# 8EncV1_3_3.net
KiCad netlist of a schematic drawn in EAGLE
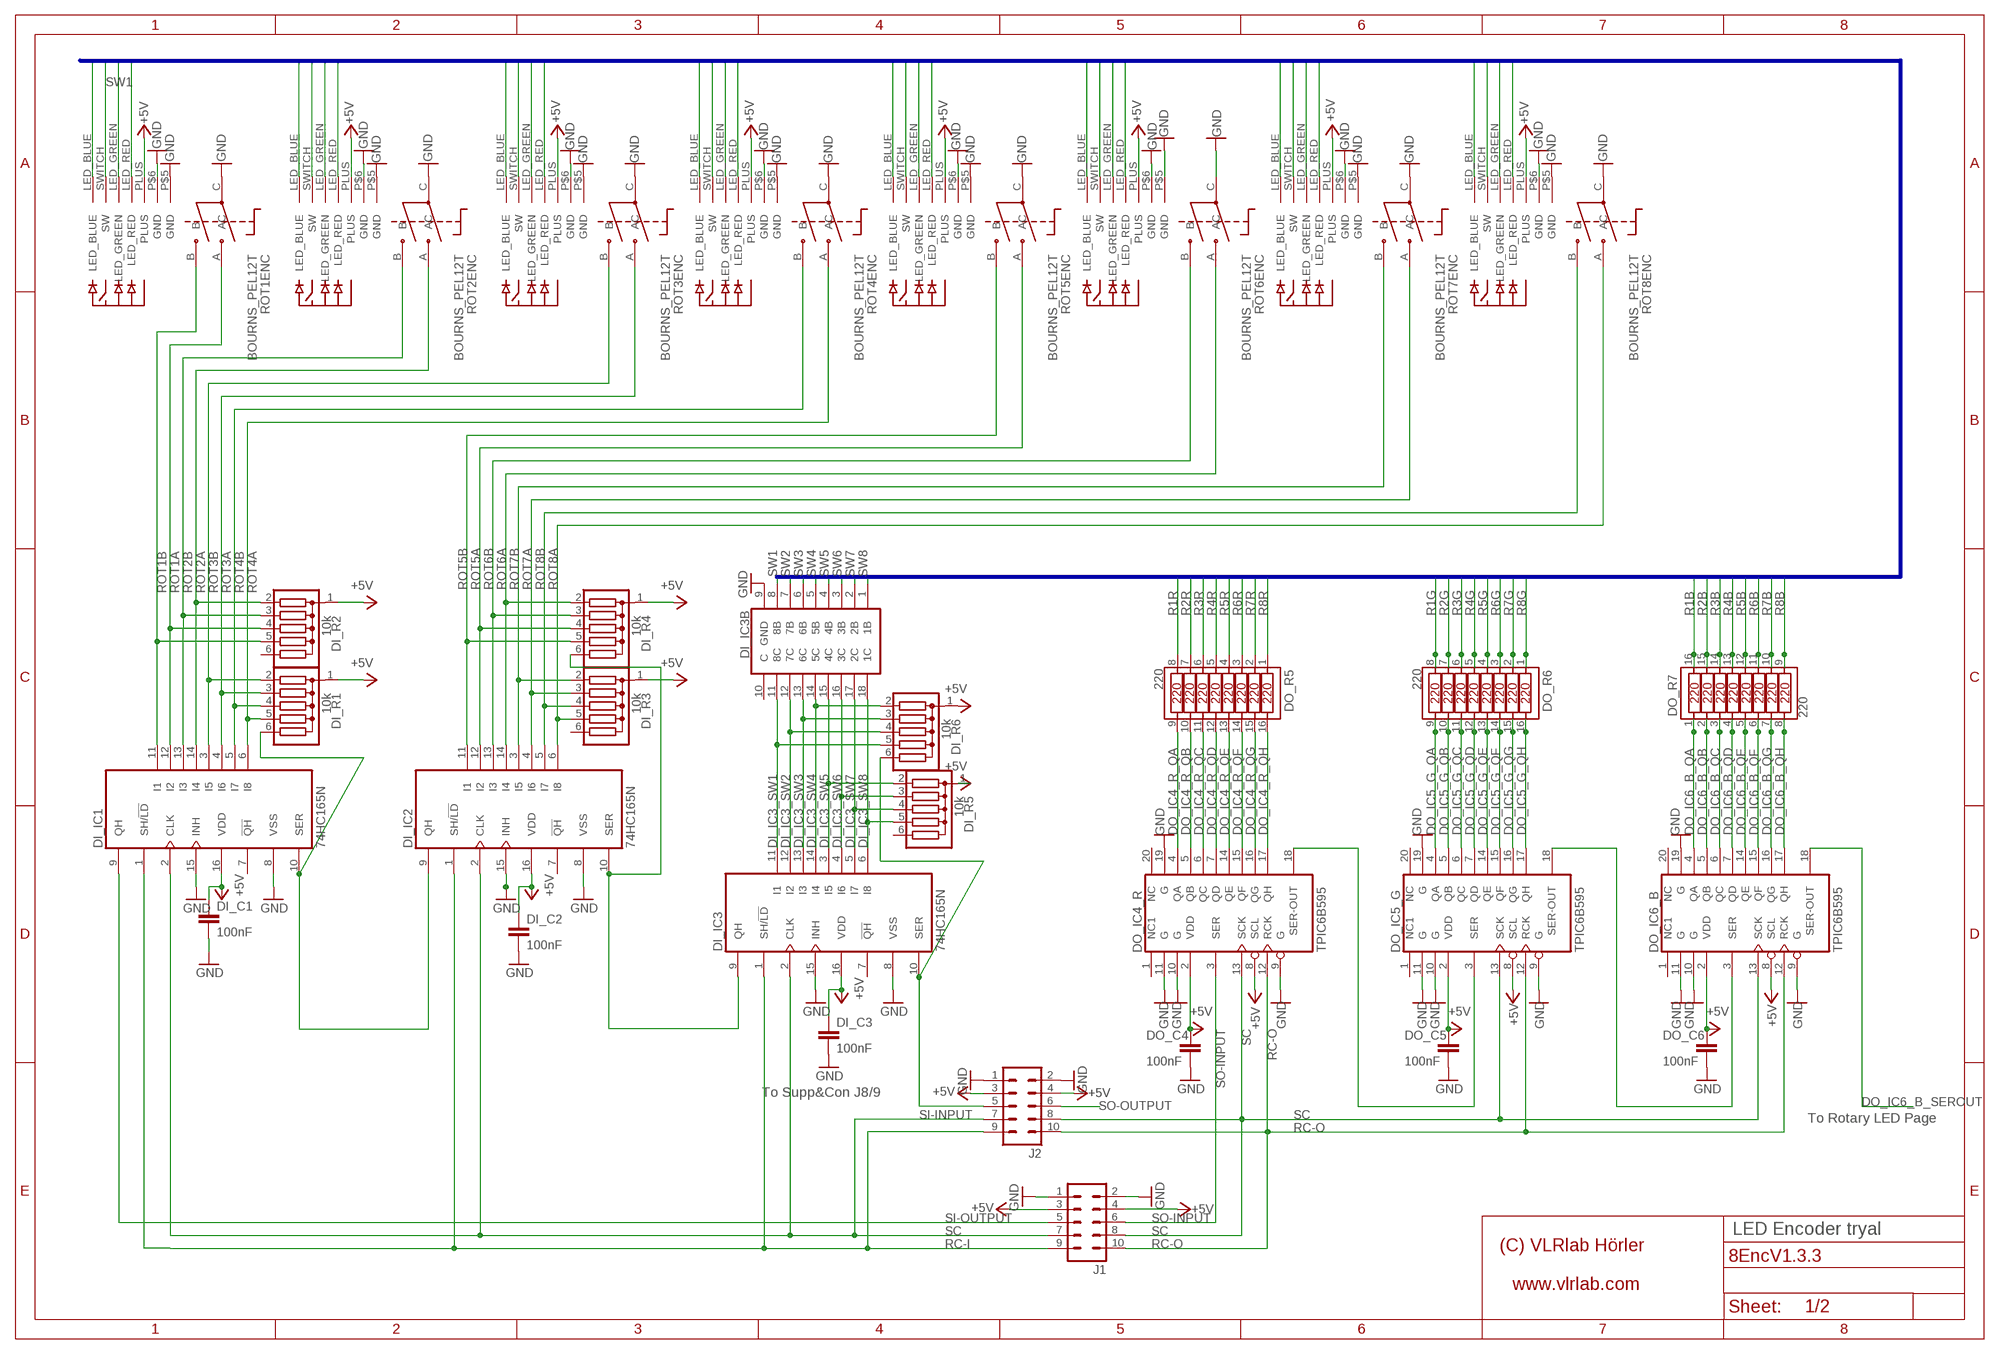
[diagram p0: schematic, sheet 1]
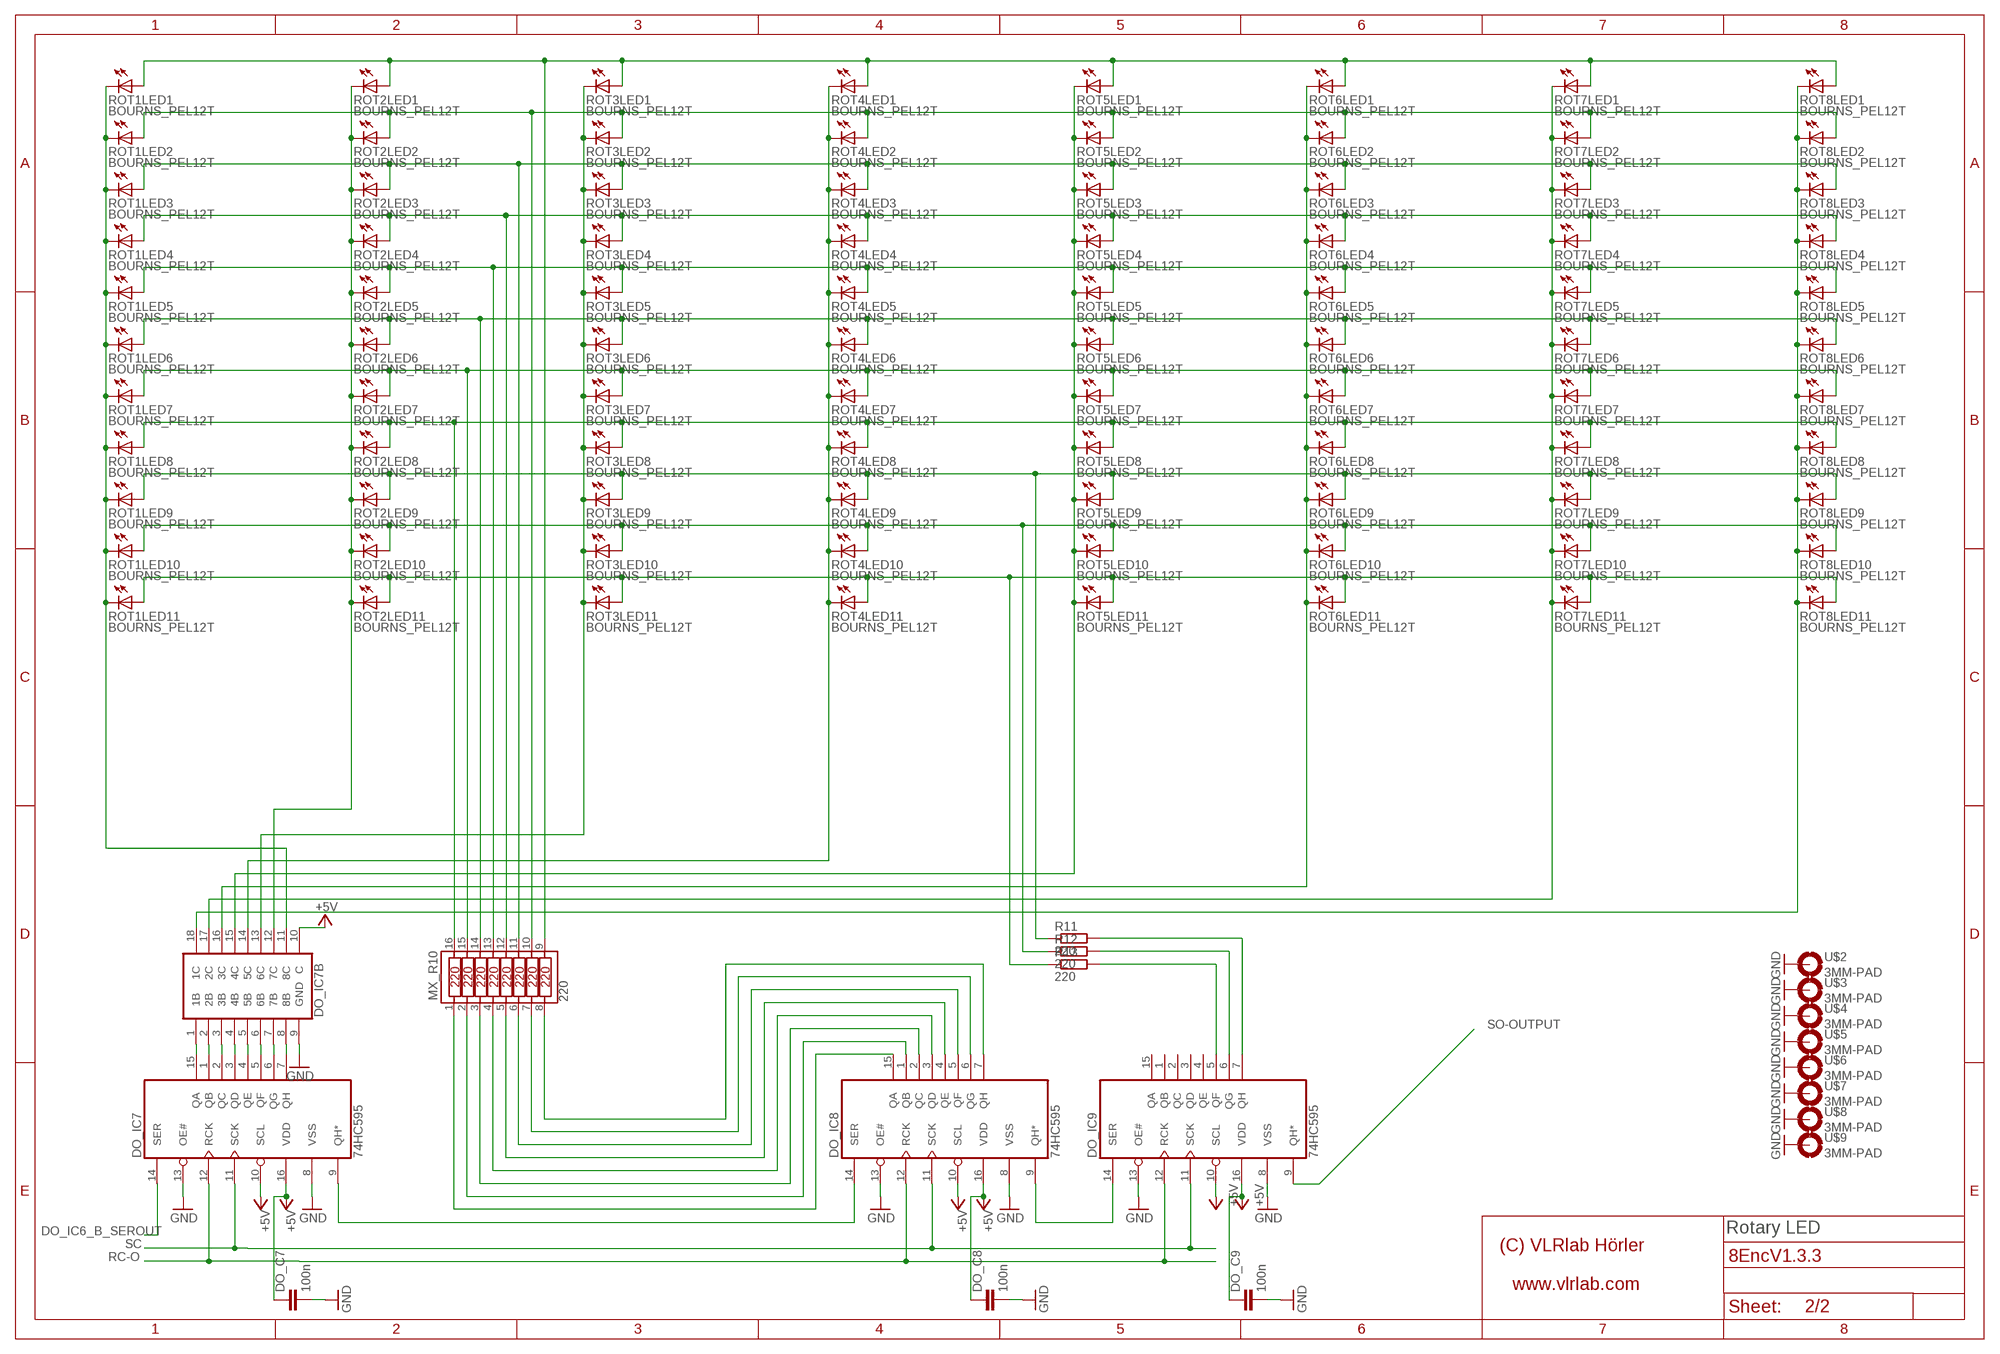
[diagram p1: schematic, sheet 2]

(export (version "E")
  (design (tool "Eeschema 10.0.6"))
  (components
    (comp (ref "DO_C7")
      (value "100n")
      (footprint "eagle-import:C025-024X044")
      (libsource (lib "eagle-import") (part "C-EU025-024X044"))
    )
    (comp (ref "DO_C8")
      (value "100n")
      (footprint "eagle-import:C025-024X044")
      (libsource (lib "eagle-import") (part "C-EU025-024X044"))
    )
    (comp (ref "DO_C9")
      (value "100n")
      (footprint "eagle-import:C025-024X044")
      (libsource (lib "eagle-import") (part "C-EU025-024X044"))
    )
    (comp (ref "DO_IC7")
      (value "74HC595")
      (footprint "eagle-import:SO16D")
      (libsource (lib "eagle-import") (part "595-541-165-uln2803_74HC595SO16D"))
    )
    (comp (ref "DO_IC7B")
      (value "ULN2803SO18W")
      (footprint "eagle-import:SO18W")
      (libsource (lib "eagle-import") (part "ULN2803SO18W"))
    )
    (comp (ref "DO_IC8")
      (value "74HC595")
      (footprint "eagle-import:SO16D")
      (libsource (lib "eagle-import") (part "595-541-165-uln2803_74HC595SO16D"))
    )
    (comp (ref "DO_IC9")
      (value "74HC595")
      (footprint "eagle-import:SO16D")
      (libsource (lib "eagle-import") (part "595-541-165-uln2803_74HC595SO16D"))
    )
    (comp (ref "MX_R10")
      (value "220")
      (footprint "eagle-import:SOIC16W")
      (libsource (lib "eagle-import") (part "4816P-1SOIC16W"))
    )
    (comp (ref "R11")
      (value "220")
      (footprint "eagle-import:0204_7")
      (libsource (lib "eagle-import") (part "R-EU_0204/7"))
    )
    (comp (ref "R12")
      (value "220")
      (footprint "eagle-import:0204_7")
      (libsource (lib "eagle-import") (part "R-EU_0204/7"))
    )
    (comp (ref "R13")
      (value "220")
      (footprint "eagle-import:0204_7")
      (libsource (lib "eagle-import") (part "R-EU_0204/7"))
    )
    (comp (ref "ROT1")
      (value "BOURNS_PEL12T")
      (footprint "eagle-import:PEL12T_11-LED-RING")
      (libsource (lib "eagle-import") (part "BOURNS_PEL12T_11-LED-RING"))
    )
    (comp (ref "ROT2")
      (value "BOURNS_PEL12T")
      (footprint "eagle-import:PEL12T_11-LED-RING")
      (libsource (lib "eagle-import") (part "BOURNS_PEL12T_11-LED-RING"))
    )
    (comp (ref "ROT3")
      (value "BOURNS_PEL12T")
      (footprint "eagle-import:PEL12T_11-LED-RING")
      (libsource (lib "eagle-import") (part "BOURNS_PEL12T_11-LED-RING"))
    )
    (comp (ref "ROT4")
      (value "BOURNS_PEL12T")
      (footprint "eagle-import:PEL12T_11-LED-RING")
      (libsource (lib "eagle-import") (part "BOURNS_PEL12T_11-LED-RING"))
    )
    (comp (ref "ROT5")
      (value "BOURNS_PEL12T")
      (footprint "eagle-import:PEL12T_11-LED-RING")
      (libsource (lib "eagle-import") (part "BOURNS_PEL12T_11-LED-RING"))
    )
    (comp (ref "ROT6")
      (value "BOURNS_PEL12T")
      (footprint "eagle-import:PEL12T_11-LED-RING")
      (libsource (lib "eagle-import") (part "BOURNS_PEL12T_11-LED-RING"))
    )
    (comp (ref "ROT7")
      (value "BOURNS_PEL12T")
      (footprint "eagle-import:PEL12T_11-LED-RING")
      (libsource (lib "eagle-import") (part "BOURNS_PEL12T_11-LED-RING"))
    )
    (comp (ref "ROT8")
      (value "BOURNS_PEL12T")
      (footprint "eagle-import:PEL12T_11-LED-RING")
      (libsource (lib "eagle-import") (part "BOURNS_PEL12T_11-LED-RING"))
    )
    (comp (ref "U$2")
      (value "3MM-PAD")
      (footprint "eagle-import:3MM-PAD")
      (libsource (lib "eagle-import") (part "3MM-PAD"))
    )
    (comp (ref "U$3")
      (value "3MM-PAD")
      (footprint "eagle-import:3MM-PAD")
      (libsource (lib "eagle-import") (part "3MM-PAD"))
    )
    (comp (ref "U$4")
      (value "3MM-PAD")
      (footprint "eagle-import:3MM-PAD")
      (libsource (lib "eagle-import") (part "3MM-PAD"))
    )
    (comp (ref "U$5")
      (value "3MM-PAD")
      (footprint "eagle-import:3MM-PAD")
      (libsource (lib "eagle-import") (part "3MM-PAD"))
    )
    (comp (ref "U$6")
      (value "3MM-PAD")
      (footprint "eagle-import:3MM-PAD")
      (libsource (lib "eagle-import") (part "3MM-PAD"))
    )
    (comp (ref "U$7")
      (value "3MM-PAD")
      (footprint "eagle-import:3MM-PAD")
      (libsource (lib "eagle-import") (part "3MM-PAD"))
    )
    (comp (ref "U$8")
      (value "3MM-PAD")
      (footprint "eagle-import:3MM-PAD")
      (libsource (lib "eagle-import") (part "3MM-PAD"))
    )
    (comp (ref "U$9")
      (value "3MM-PAD")
      (footprint "eagle-import:3MM-PAD")
      (libsource (lib "eagle-import") (part "3MM-PAD"))
    )
    (comp (ref "DI_C1")
      (value "100nF")
      (footprint "eagle-import:C025-024X044")
      (libsource (lib "eagle-import") (part "C-EU025-024X044"))
    )
    (comp (ref "DI_C2")
      (value "100nF")
      (footprint "eagle-import:C025-024X044")
      (libsource (lib "eagle-import") (part "C-EU025-024X044"))
    )
    (comp (ref "DI_C3")
      (value "100nF")
      (footprint "eagle-import:C025-024X044")
      (libsource (lib "eagle-import") (part "C-EU025-024X044"))
    )
    (comp (ref "DI_IC1")
      (value "74HC165N")
      (footprint "eagle-import:SO16D")
      (libsource (lib "eagle-import") (part "74HC165NSO16D"))
    )
    (comp (ref "DI_IC2")
      (value "74HC165N")
      (footprint "eagle-import:SO16D")
      (libsource (lib "eagle-import") (part "74HC165NSO16D"))
    )
    (comp (ref "DI_IC3")
      (value "74HC165N")
      (footprint "eagle-import:SO16D")
      (libsource (lib "eagle-import") (part "74HC165NSO16D"))
    )
    (comp (ref "DI_IC3B")
      (value "ULN2803SO18W")
      (footprint "eagle-import:SO18W")
      (libsource (lib "eagle-import") (part "ULN2803SO18W"))
    )
    (comp (ref "DI_R1")
      (value "10k")
      (footprint "eagle-import:SIL6")
      (libsource (lib "eagle-import") (part "4306R"))
    )
    (comp (ref "DI_R2")
      (value "10k")
      (footprint "eagle-import:SIL6")
      (libsource (lib "eagle-import") (part "4306R"))
    )
    (comp (ref "DI_R3")
      (value "10k")
      (footprint "eagle-import:SIL6")
      (libsource (lib "eagle-import") (part "4306R"))
    )
    (comp (ref "DI_R4")
      (value "10k")
      (footprint "eagle-import:SIL6")
      (libsource (lib "eagle-import") (part "4306R"))
    )
    (comp (ref "DI_R5")
      (value "10k")
      (footprint "eagle-import:SIL6")
      (libsource (lib "eagle-import") (part "4306R"))
    )
    (comp (ref "DI_R6")
      (value "10k")
      (footprint "eagle-import:SIL6")
      (libsource (lib "eagle-import") (part "4306R"))
    )
    (comp (ref "DO_C4")
      (value "100nF")
      (footprint "eagle-import:C025-024X044")
      (libsource (lib "eagle-import") (part "C-EU025-024X044"))
    )
    (comp (ref "DO_C5")
      (value "100nF")
      (footprint "eagle-import:C025-024X044")
      (libsource (lib "eagle-import") (part "C-EU025-024X044"))
    )
    (comp (ref "DO_C6")
      (value "100nF")
      (footprint "eagle-import:C025-024X044")
      (libsource (lib "eagle-import") (part "C-EU025-024X044"))
    )
    (comp (ref "DO_IC4_R")
      (value "TPIC6B595")
      (footprint "eagle-import:SO20W")
      (libsource (lib "eagle-import") (part "TPIC6B595SO20W"))
    )
    (comp (ref "DO_IC5_G")
      (value "TPIC6B595")
      (footprint "eagle-import:SO20W")
      (libsource (lib "eagle-import") (part "TPIC6B595SO20W"))
    )
    (comp (ref "DO_IC6_B")
      (value "TPIC6B595")
      (footprint "eagle-import:SO20W")
      (libsource (lib "eagle-import") (part "TPIC6B595SO20W"))
    )
    (comp (ref "DO_R5")
      (value "220")
      (footprint "eagle-import:SOIC16W")
      (libsource (lib "eagle-import") (part "4816P-1SOIC16W"))
    )
    (comp (ref "DO_R6")
      (value "220")
      (footprint "eagle-import:SOIC16W")
      (libsource (lib "eagle-import") (part "4816P-1SOIC16W"))
    )
    (comp (ref "DO_R7")
      (value "220")
      (footprint "eagle-import:SOIC16W")
      (libsource (lib "eagle-import") (part "4816P-1SOIC16W"))
    )
    (comp (ref "J1")
      (value "ML10")
      (footprint "eagle-import:ML10")
      (libsource (lib "eagle-import") (part "ML10"))
    )
    (comp (ref "J2")
      (value "ML10")
      (footprint "eagle-import:ML10")
      (libsource (lib "eagle-import") (part "ML10"))
    )
  )
  (nets
    (net (code "1") (name "+5V") (class "Default")
      (node (ref "DI_C1") (pin "1") (pinfunction "1_1") (pintype "passive"))
      (node (ref "DI_C2") (pin "1") (pinfunction "1_1") (pintype "passive"))
      (node (ref "DI_C3") (pin "1") (pinfunction "1_1") (pintype "passive"))
      (node (ref "DI_IC1") (pin "16") (pinfunction "VDD_16") (pintype "power_in"))
      (node (ref "DI_IC2") (pin "16") (pinfunction "VDD_16") (pintype "power_in"))
      (node (ref "DI_IC3") (pin "16") (pinfunction "VDD_16") (pintype "power_in"))
      (node (ref "DI_R1") (pin "1") (pinfunction "1_1") (pintype "passive"))
      (node (ref "DI_R2") (pin "1") (pinfunction "1_1") (pintype "passive"))
      (node (ref "DI_R3") (pin "1") (pinfunction "1_1") (pintype "passive"))
      (node (ref "DI_R4") (pin "1") (pinfunction "1_1") (pintype "passive"))
      (node (ref "DI_R5") (pin "1") (pinfunction "1_1") (pintype "passive"))
      (node (ref "DI_R6") (pin "1") (pinfunction "1_1") (pintype "passive"))
      (node (ref "DO_C4") (pin "1") (pinfunction "1_1") (pintype "passive"))
      (node (ref "DO_C5") (pin "1") (pinfunction "1_1") (pintype "passive"))
      (node (ref "DO_C6") (pin "1") (pinfunction "1_1") (pintype "passive"))
      (node (ref "DO_C7") (pin "1") (pinfunction "1_1") (pintype "passive"))
      (node (ref "DO_C8") (pin "1") (pinfunction "1_1") (pintype "passive"))
      (node (ref "DO_C9") (pin "1") (pinfunction "1_1") (pintype "passive"))
      (node (ref "DO_IC4_R") (pin "2") (pinfunction "VDD_2") (pintype "power_in"))
      (node (ref "DO_IC4_R") (pin "8") (pinfunction "SCL_8") (pintype "input"))
      (node (ref "DO_IC5_G") (pin "2") (pinfunction "VDD_2") (pintype "power_in"))
      (node (ref "DO_IC5_G") (pin "8") (pinfunction "SCL_8") (pintype "input"))
      (node (ref "DO_IC6_B") (pin "2") (pinfunction "VDD_2") (pintype "power_in"))
      (node (ref "DO_IC6_B") (pin "8") (pinfunction "SCL_8") (pintype "input"))
      (node (ref "DO_IC7") (pin "10") (pinfunction "SCL_10") (pintype "input"))
      (node (ref "DO_IC7") (pin "16") (pinfunction "VDD_16") (pintype "power_in"))
      (node (ref "DO_IC7B") (pin "10") (pinfunction "C_10") (pintype "passive"))
      (node (ref "DO_IC8") (pin "10") (pinfunction "SCL_10") (pintype "input"))
      (node (ref "DO_IC8") (pin "16") (pinfunction "VDD_16") (pintype "power_in"))
      (node (ref "DO_IC9") (pin "10") (pinfunction "SCL_10") (pintype "input"))
      (node (ref "DO_IC9") (pin "16") (pinfunction "VDD_16") (pintype "power_in"))
      (node (ref "J1") (pin "3") (pinfunction "3_3") (pintype "passive"))
      (node (ref "J1") (pin "4") (pinfunction "4_4") (pintype "passive"))
      (node (ref "J2") (pin "3") (pinfunction "3_3") (pintype "passive"))
      (node (ref "J2") (pin "4") (pinfunction "4_4") (pintype "passive"))
      (node (ref "ROT1") (pin "PLUS") (pinfunction "PLUS_PLUS") (pintype "bidirectional"))
      (node (ref "ROT2") (pin "PLUS") (pinfunction "PLUS_PLUS") (pintype "bidirectional"))
      (node (ref "ROT3") (pin "PLUS") (pinfunction "PLUS_PLUS") (pintype "bidirectional"))
      (node (ref "ROT4") (pin "PLUS") (pinfunction "PLUS_PLUS") (pintype "bidirectional"))
      (node (ref "ROT5") (pin "PLUS") (pinfunction "PLUS_PLUS") (pintype "bidirectional"))
      (node (ref "ROT6") (pin "PLUS") (pinfunction "PLUS_PLUS") (pintype "bidirectional"))
      (node (ref "ROT7") (pin "PLUS") (pinfunction "PLUS_PLUS") (pintype "bidirectional"))
      (node (ref "ROT8") (pin "PLUS") (pinfunction "PLUS_PLUS") (pintype "bidirectional"))
    )
    (net (code "2") (name "DI_IC3_SW1") (class "Default")
      (node (ref "DI_IC3") (pin "11") (pinfunction "I1_11") (pintype "input"))
      (node (ref "DI_IC3B") (pin "11") (pinfunction "8C_11") (pintype "open_collector"))
      (node (ref "DI_R6") (pin "5") (pinfunction "5_5") (pintype "passive"))
    )
    (net (code "3") (name "DI_IC3_SW2") (class "Default")
      (node (ref "DI_IC3") (pin "12") (pinfunction "I2_12") (pintype "input"))
      (node (ref "DI_IC3B") (pin "12") (pinfunction "7C_12") (pintype "open_collector"))
      (node (ref "DI_R6") (pin "4") (pinfunction "4_4") (pintype "passive"))
    )
    (net (code "4") (name "DI_IC3_SW3") (class "Default")
      (node (ref "DI_IC3") (pin "13") (pinfunction "I3_13") (pintype "input"))
      (node (ref "DI_IC3B") (pin "13") (pinfunction "6C_13") (pintype "open_collector"))
      (node (ref "DI_R6") (pin "3") (pinfunction "3_3") (pintype "passive"))
    )
    (net (code "5") (name "DI_IC3_SW4") (class "Default")
      (node (ref "DI_IC3") (pin "14") (pinfunction "I4_14") (pintype "input"))
      (node (ref "DI_IC3B") (pin "14") (pinfunction "5C_14") (pintype "open_collector"))
      (node (ref "DI_R6") (pin "2") (pinfunction "2_2") (pintype "passive"))
    )
    (net (code "6") (name "DI_IC3_SW5") (class "Default")
      (node (ref "DI_IC3") (pin "3") (pinfunction "I5_3") (pintype "input"))
      (node (ref "DI_IC3B") (pin "15") (pinfunction "4C_15") (pintype "open_collector"))
      (node (ref "DI_R5") (pin "2") (pinfunction "2_2") (pintype "passive"))
    )
    (net (code "7") (name "DI_IC3_SW6") (class "Default")
      (node (ref "DI_IC3") (pin "4") (pinfunction "I6_4") (pintype "input"))
      (node (ref "DI_IC3B") (pin "16") (pinfunction "3C_16") (pintype "open_collector"))
      (node (ref "DI_R5") (pin "3") (pinfunction "3_3") (pintype "passive"))
    )
    (net (code "8") (name "DI_IC3_SW7") (class "Default")
      (node (ref "DI_IC3") (pin "5") (pinfunction "I7_5") (pintype "input"))
      (node (ref "DI_IC3B") (pin "17") (pinfunction "2C_17") (pintype "open_collector"))
      (node (ref "DI_R5") (pin "4") (pinfunction "4_4") (pintype "passive"))
    )
    (net (code "9") (name "DI_IC3_SW8") (class "Default")
      (node (ref "DI_IC3") (pin "6") (pinfunction "I8_6") (pintype "input"))
      (node (ref "DI_IC3B") (pin "18") (pinfunction "1C_18") (pintype "open_collector"))
      (node (ref "DI_R5") (pin "5") (pinfunction "5_5") (pintype "passive"))
    )
    (net (code "10") (name "DO_IC4_R_QA") (class "Default")
      (node (ref "DO_IC4_R") (pin "4") (pinfunction "QA_4") (pintype "tri_state"))
      (node (ref "DO_R5") (pin "9") (pinfunction "P$9_9") (pintype "passive"))
    )
    (net (code "11") (name "DO_IC4_R_QB") (class "Default")
      (node (ref "DO_IC4_R") (pin "5") (pinfunction "QB_5") (pintype "tri_state"))
      (node (ref "DO_R5") (pin "10") (pinfunction "P$10_10") (pintype "passive"))
    )
    (net (code "12") (name "DO_IC4_R_QC") (class "Default")
      (node (ref "DO_IC4_R") (pin "6") (pinfunction "QC_6") (pintype "tri_state"))
      (node (ref "DO_R5") (pin "11") (pinfunction "P$11_11") (pintype "passive"))
    )
    (net (code "13") (name "DO_IC4_R_QD") (class "Default")
      (node (ref "DO_IC4_R") (pin "7") (pinfunction "QD_7") (pintype "tri_state"))
      (node (ref "DO_R5") (pin "12") (pinfunction "P$12_12") (pintype "passive"))
    )
    (net (code "14") (name "DO_IC4_R_QE") (class "Default")
      (node (ref "DO_IC4_R") (pin "14") (pinfunction "QE_14") (pintype "tri_state"))
      (node (ref "DO_R5") (pin "13") (pinfunction "P$13_13") (pintype "passive"))
    )
    (net (code "15") (name "DO_IC4_R_QF") (class "Default")
      (node (ref "DO_IC4_R") (pin "15") (pinfunction "QF_15") (pintype "tri_state"))
      (node (ref "DO_R5") (pin "14") (pinfunction "P$14_14") (pintype "passive"))
    )
    (net (code "16") (name "DO_IC4_R_QG") (class "Default")
      (node (ref "DO_IC4_R") (pin "16") (pinfunction "QG_16") (pintype "tri_state"))
      (node (ref "DO_R5") (pin "15") (pinfunction "P$15_15") (pintype "passive"))
    )
    (net (code "17") (name "DO_IC4_R_QH") (class "Default")
      (node (ref "DO_IC4_R") (pin "17") (pinfunction "QH_17") (pintype "tri_state"))
      (node (ref "DO_R5") (pin "16") (pinfunction "P$16_16") (pintype "passive"))
    )
    (net (code "18") (name "DO_IC5_G_QA") (class "Default")
      (node (ref "DO_IC5_G") (pin "4") (pinfunction "QA_4") (pintype "tri_state"))
      (node (ref "DO_R6") (pin "9") (pinfunction "P$9_9") (pintype "passive"))
    )
    (net (code "19") (name "DO_IC5_G_QB") (class "Default")
      (node (ref "DO_IC5_G") (pin "5") (pinfunction "QB_5") (pintype "tri_state"))
      (node (ref "DO_R6") (pin "10") (pinfunction "P$10_10") (pintype "passive"))
    )
    (net (code "20") (name "DO_IC5_G_QC") (class "Default")
      (node (ref "DO_IC5_G") (pin "6") (pinfunction "QC_6") (pintype "tri_state"))
      (node (ref "DO_R6") (pin "11") (pinfunction "P$11_11") (pintype "passive"))
    )
    (net (code "21") (name "DO_IC5_G_QD") (class "Default")
      (node (ref "DO_IC5_G") (pin "7") (pinfunction "QD_7") (pintype "tri_state"))
      (node (ref "DO_R6") (pin "12") (pinfunction "P$12_12") (pintype "passive"))
    )
    (net (code "22") (name "DO_IC5_G_QE") (class "Default")
      (node (ref "DO_IC5_G") (pin "14") (pinfunction "QE_14") (pintype "tri_state"))
      (node (ref "DO_R6") (pin "13") (pinfunction "P$13_13") (pintype "passive"))
    )
    (net (code "23") (name "DO_IC5_G_QF") (class "Default")
      (node (ref "DO_IC5_G") (pin "15") (pinfunction "QF_15") (pintype "tri_state"))
      (node (ref "DO_R6") (pin "14") (pinfunction "P$14_14") (pintype "passive"))
    )
    (net (code "24") (name "DO_IC5_G_QG") (class "Default")
      (node (ref "DO_IC5_G") (pin "16") (pinfunction "QG_16") (pintype "tri_state"))
      (node (ref "DO_R6") (pin "15") (pinfunction "P$15_15") (pintype "passive"))
    )
    (net (code "25") (name "DO_IC5_G_QH") (class "Default")
      (node (ref "DO_IC5_G") (pin "17") (pinfunction "QH_17") (pintype "tri_state"))
      (node (ref "DO_R6") (pin "16") (pinfunction "P$16_16") (pintype "passive"))
    )
    (net (code "26") (name "DO_IC6_B_QA") (class "Default")
      (node (ref "DO_IC6_B") (pin "4") (pinfunction "QA_4") (pintype "tri_state"))
      (node (ref "DO_R7") (pin "1") (pinfunction "P$1_1") (pintype "passive"))
    )
    (net (code "27") (name "DO_IC6_B_QB") (class "Default")
      (node (ref "DO_IC6_B") (pin "5") (pinfunction "QB_5") (pintype "tri_state"))
      (node (ref "DO_R7") (pin "2") (pinfunction "P$2_2") (pintype "passive"))
    )
    (net (code "28") (name "DO_IC6_B_QC") (class "Default")
      (node (ref "DO_IC6_B") (pin "6") (pinfunction "QC_6") (pintype "tri_state"))
      (node (ref "DO_R7") (pin "3") (pinfunction "P$3_3") (pintype "passive"))
    )
    (net (code "29") (name "DO_IC6_B_QD") (class "Default")
      (node (ref "DO_IC6_B") (pin "7") (pinfunction "QD_7") (pintype "tri_state"))
      (node (ref "DO_R7") (pin "4") (pinfunction "P$4_4") (pintype "passive"))
    )
    (net (code "30") (name "DO_IC6_B_QE") (class "Default")
      (node (ref "DO_IC6_B") (pin "14") (pinfunction "QE_14") (pintype "tri_state"))
      (node (ref "DO_R7") (pin "5") (pinfunction "P$5_5") (pintype "passive"))
    )
    (net (code "31") (name "DO_IC6_B_QF") (class "Default")
      (node (ref "DO_IC6_B") (pin "15") (pinfunction "QF_15") (pintype "tri_state"))
      (node (ref "DO_R7") (pin "6") (pinfunction "P$6_6") (pintype "passive"))
    )
    (net (code "32") (name "DO_IC6_B_QG") (class "Default")
      (node (ref "DO_IC6_B") (pin "16") (pinfunction "QG_16") (pintype "tri_state"))
      (node (ref "DO_R7") (pin "7") (pinfunction "P$7_7") (pintype "passive"))
    )
    (net (code "33") (name "DO_IC6_B_QH") (class "Default")
      (node (ref "DO_IC6_B") (pin "17") (pinfunction "QH_17") (pintype "tri_state"))
      (node (ref "DO_R7") (pin "8") (pinfunction "P$8_8") (pintype "passive"))
    )
    (net (code "34") (name "DO_IC6_B_SEROUT") (class "Default")
      (node (ref "DO_IC6_B") (pin "18") (pinfunction "SER-OUT_18") (pintype "tri_state"))
      (node (ref "DO_IC7") (pin "14") (pinfunction "SER_14") (pintype "input"))
    )
    (net (code "35") (name "GND") (class "Default")
      (node (ref "DI_C1") (pin "2") (pinfunction "2_2") (pintype "passive"))
      (node (ref "DI_C2") (pin "2") (pinfunction "2_2") (pintype "passive"))
      (node (ref "DI_C3") (pin "2") (pinfunction "2_2") (pintype "passive"))
      (node (ref "DI_IC1") (pin "15") (pinfunction "INH_15") (pintype "input"))
      (node (ref "DI_IC1") (pin "8") (pinfunction "VSS_8") (pintype "power_in"))
      (node (ref "DI_IC2") (pin "15") (pinfunction "INH_15") (pintype "input"))
      (node (ref "DI_IC2") (pin "8") (pinfunction "VSS_8") (pintype "power_in"))
      (node (ref "DI_IC3") (pin "15") (pinfunction "INH_15") (pintype "input"))
      (node (ref "DI_IC3") (pin "8") (pinfunction "VSS_8") (pintype "power_in"))
      (node (ref "DI_IC3B") (pin "9") (pinfunction "GND_9") (pintype "power_in"))
      (node (ref "DO_C4") (pin "2") (pinfunction "2_2") (pintype "passive"))
      (node (ref "DO_C5") (pin "2") (pinfunction "2_2") (pintype "passive"))
      (node (ref "DO_C6") (pin "2") (pinfunction "2_2") (pintype "passive"))
      (node (ref "DO_C7") (pin "2") (pinfunction "2_2") (pintype "passive"))
      (node (ref "DO_C8") (pin "2") (pinfunction "2_2") (pintype "passive"))
      (node (ref "DO_C9") (pin "2") (pinfunction "2_2") (pintype "passive"))
      (node (ref "DO_IC4_R") (pin "10") (pinfunction "G_10") (pintype "power_in"))
      (node (ref "DO_IC4_R") (pin "11") (pinfunction "G_11") (pintype "power_in"))
      (node (ref "DO_IC4_R") (pin "19") (pinfunction "G_19") (pintype "tri_state"))
      (node (ref "DO_IC4_R") (pin "9") (pinfunction "G_9") (pintype "input"))
      (node (ref "DO_IC5_G") (pin "10") (pinfunction "G_10") (pintype "power_in"))
      (node (ref "DO_IC5_G") (pin "11") (pinfunction "G_11") (pintype "power_in"))
      (node (ref "DO_IC5_G") (pin "19") (pinfunction "G_19") (pintype "tri_state"))
      (node (ref "DO_IC5_G") (pin "9") (pinfunction "G_9") (pintype "input"))
      (node (ref "DO_IC6_B") (pin "10") (pinfunction "G_10") (pintype "power_in"))
      (node (ref "DO_IC6_B") (pin "11") (pinfunction "G_11") (pintype "power_in"))
      (node (ref "DO_IC6_B") (pin "19") (pinfunction "G_19") (pintype "tri_state"))
      (node (ref "DO_IC6_B") (pin "9") (pinfunction "G_9") (pintype "input"))
      (node (ref "DO_IC7") (pin "13") (pinfunction "OE#_13") (pintype "input"))
      (node (ref "DO_IC7") (pin "8") (pinfunction "VSS_8") (pintype "power_in"))
      (node (ref "DO_IC7B") (pin "9") (pinfunction "GND_9") (pintype "power_in"))
      (node (ref "DO_IC8") (pin "13") (pinfunction "OE#_13") (pintype "input"))
      (node (ref "DO_IC8") (pin "8") (pinfunction "VSS_8") (pintype "power_in"))
      (node (ref "DO_IC9") (pin "13") (pinfunction "OE#_13") (pintype "input"))
      (node (ref "DO_IC9") (pin "8") (pinfunction "VSS_8") (pintype "power_in"))
      (node (ref "J1") (pin "1") (pinfunction "1_1") (pintype "passive"))
      (node (ref "J1") (pin "2") (pinfunction "2_2") (pintype "passive"))
      (node (ref "J2") (pin "1") (pinfunction "1_1") (pintype "passive"))
      (node (ref "J2") (pin "2") (pinfunction "2_2") (pintype "passive"))
      (node (ref "ROT1") (pin "C") (pinfunction "C_C") (pintype "bidirectional"))
      (node (ref "ROT1") (pin "P$5") (pinfunction "GND_P$5") (pintype "bidirectional"))
      (node (ref "ROT1") (pin "P$6") (pinfunction "GND_P$6") (pintype "bidirectional"))
      (node (ref "ROT2") (pin "C") (pinfunction "C_C") (pintype "bidirectional"))
      (node (ref "ROT2") (pin "P$5") (pinfunction "GND_P$5") (pintype "bidirectional"))
      (node (ref "ROT2") (pin "P$6") (pinfunction "GND_P$6") (pintype "bidirectional"))
      (node (ref "ROT3") (pin "C") (pinfunction "C_C") (pintype "bidirectional"))
      (node (ref "ROT3") (pin "P$5") (pinfunction "GND_P$5") (pintype "bidirectional"))
      (node (ref "ROT3") (pin "P$6") (pinfunction "GND_P$6") (pintype "bidirectional"))
      (node (ref "ROT4") (pin "C") (pinfunction "C_C") (pintype "bidirectional"))
      (node (ref "ROT4") (pin "P$5") (pinfunction "GND_P$5") (pintype "bidirectional"))
      (node (ref "ROT4") (pin "P$6") (pinfunction "GND_P$6") (pintype "bidirectional"))
      (node (ref "ROT5") (pin "C") (pinfunction "C_C") (pintype "bidirectional"))
      (node (ref "ROT5") (pin "P$5") (pinfunction "GND_P$5") (pintype "bidirectional"))
      (node (ref "ROT5") (pin "P$6") (pinfunction "GND_P$6") (pintype "bidirectional"))
      (node (ref "ROT6") (pin "C") (pinfunction "C_C") (pintype "bidirectional"))
      (node (ref "ROT6") (pin "P$5") (pinfunction "GND_P$5") (pintype "bidirectional"))
      (node (ref "ROT6") (pin "P$6") (pinfunction "GND_P$6") (pintype "bidirectional"))
      (node (ref "ROT7") (pin "C") (pinfunction "C_C") (pintype "bidirectional"))
      (node (ref "ROT7") (pin "P$5") (pinfunction "GND_P$5") (pintype "bidirectional"))
      (node (ref "ROT7") (pin "P$6") (pinfunction "GND_P$6") (pintype "bidirectional"))
      (node (ref "ROT8") (pin "C") (pinfunction "C_C") (pintype "bidirectional"))
      (node (ref "ROT8") (pin "P$5") (pinfunction "GND_P$5") (pintype "bidirectional"))
      (node (ref "ROT8") (pin "P$6") (pinfunction "GND_P$6") (pintype "bidirectional"))
      (node (ref "U$2") (pin "B3") (pinfunction "MOUNT_B3") (pintype "passive"))
      (node (ref "U$3") (pin "B3") (pinfunction "MOUNT_B3") (pintype "passive"))
      (node (ref "U$4") (pin "B3") (pinfunction "MOUNT_B3") (pintype "passive"))
      (node (ref "U$5") (pin "B3") (pinfunction "MOUNT_B3") (pintype "passive"))
      (node (ref "U$6") (pin "B3") (pinfunction "MOUNT_B3") (pintype "passive"))
      (node (ref "U$7") (pin "B3") (pinfunction "MOUNT_B3") (pintype "passive"))
      (node (ref "U$8") (pin "B3") (pinfunction "MOUNT_B3") (pintype "passive"))
      (node (ref "U$9") (pin "B3") (pinfunction "MOUNT_B3") (pintype "passive"))
    )
    (net (code "36") (name "Net-(DI_IC1-SER)") (class "Default")
      (node (ref "DI_IC1") (pin "10") (pinfunction "SER_10") (pintype "input"))
      (node (ref "DI_IC2") (pin "9") (pinfunction "QH_9") (pintype "output"))
      (node (ref "DI_R1") (pin "6") (pinfunction "6_6") (pintype "passive"))
    )
    (net (code "37") (name "Net-(DI_IC2-SER)") (class "Default")
      (node (ref "DI_IC2") (pin "10") (pinfunction "SER_10") (pintype "input"))
      (node (ref "DI_IC3") (pin "9") (pinfunction "QH_9") (pintype "output"))
      (node (ref "DI_R4") (pin "6") (pinfunction "6_6") (pintype "passive"))
    )
    (net (code "38") (name "Net-(DO_IC4_R-SER-OUT)") (class "Default")
      (node (ref "DO_IC4_R") (pin "18") (pinfunction "SER-OUT_18") (pintype "tri_state"))
      (node (ref "DO_IC5_G") (pin "3") (pinfunction "SER_3") (pintype "input"))
    )
    (net (code "39") (name "Net-(DO_IC5_G-SER-OUT)") (class "Default")
      (node (ref "DO_IC5_G") (pin "18") (pinfunction "SER-OUT_18") (pintype "tri_state"))
      (node (ref "DO_IC6_B") (pin "3") (pinfunction "SER_3") (pintype "input"))
    )
    (net (code "40") (name "Net-(DO_IC7-QA)") (class "Default")
      (node (ref "DO_IC7") (pin "15") (pinfunction "QA_15") (pintype "tri_state"))
      (node (ref "DO_IC7B") (pin "1") (pinfunction "1B_1") (pintype "input"))
    )
    (net (code "41") (name "Net-(DO_IC7-QB)") (class "Default")
      (node (ref "DO_IC7") (pin "1") (pinfunction "QB_1") (pintype "tri_state"))
      (node (ref "DO_IC7B") (pin "2") (pinfunction "2B_2") (pintype "input"))
    )
    (net (code "42") (name "Net-(DO_IC7-QC)") (class "Default")
      (node (ref "DO_IC7") (pin "2") (pinfunction "QC_2") (pintype "tri_state"))
      (node (ref "DO_IC7B") (pin "3") (pinfunction "3B_3") (pintype "input"))
    )
    (net (code "43") (name "Net-(DO_IC7-QD)") (class "Default")
      (node (ref "DO_IC7") (pin "3") (pinfunction "QD_3") (pintype "tri_state"))
      (node (ref "DO_IC7B") (pin "4") (pinfunction "4B_4") (pintype "input"))
    )
    (net (code "44") (name "Net-(DO_IC7-QE)") (class "Default")
      (node (ref "DO_IC7") (pin "4") (pinfunction "QE_4") (pintype "tri_state"))
      (node (ref "DO_IC7B") (pin "5") (pinfunction "5B_5") (pintype "input"))
    )
    (net (code "45") (name "Net-(DO_IC7-QF)") (class "Default")
      (node (ref "DO_IC7") (pin "5") (pinfunction "QF_5") (pintype "tri_state"))
      (node (ref "DO_IC7B") (pin "6") (pinfunction "6B_6") (pintype "input"))
    )
    (net (code "46") (name "Net-(DO_IC7-QG)") (class "Default")
      (node (ref "DO_IC7") (pin "6") (pinfunction "QG_6") (pintype "tri_state"))
      (node (ref "DO_IC7B") (pin "7") (pinfunction "7B_7") (pintype "input"))
    )
    (net (code "47") (name "Net-(DO_IC7-QH)") (class "Default")
      (node (ref "DO_IC7") (pin "7") (pinfunction "QH_7") (pintype "tri_state"))
      (node (ref "DO_IC7B") (pin "8") (pinfunction "8B_8") (pintype "input"))
    )
    (net (code "48") (name "Net-(DO_IC7-QH*)") (class "Default")
      (node (ref "DO_IC7") (pin "9") (pinfunction "QH*_9") (pintype "tri_state"))
      (node (ref "DO_IC8") (pin "14") (pinfunction "SER_14") (pintype "input"))
    )
    (net (code "49") (name "Net-(DO_IC7B-1C)") (class "Default")
      (node (ref "DO_IC7B") (pin "18") (pinfunction "1C_18") (pintype "open_collector"))
      (node (ref "ROT8") (pin "K1") (pinfunction "C_K1") (pintype "passive"))
      (node (ref "ROT8") (pin "K10") (pinfunction "C_K10") (pintype "passive"))
      (node (ref "ROT8") (pin "K12") (pinfunction "C_K12") (pintype "passive"))
      (node (ref "ROT8") (pin "K2") (pinfunction "C_K2") (pintype "passive"))
      (node (ref "ROT8") (pin "K3") (pinfunction "C_K3") (pintype "passive"))
      (node (ref "ROT8") (pin "K4") (pinfunction "C_K4") (pintype "passive"))
      (node (ref "ROT8") (pin "K5") (pinfunction "C_K5") (pintype "passive"))
      (node (ref "ROT8") (pin "K6") (pinfunction "C_K6") (pintype "passive"))
      (node (ref "ROT8") (pin "K7") (pinfunction "C_K7") (pintype "passive"))
      (node (ref "ROT8") (pin "K8") (pinfunction "C_K8") (pintype "passive"))
      (node (ref "ROT8") (pin "K9") (pinfunction "C_K9") (pintype "passive"))
    )
    (net (code "50") (name "Net-(DO_IC7B-2C)") (class "Default")
      (node (ref "DO_IC7B") (pin "17") (pinfunction "2C_17") (pintype "open_collector"))
      (node (ref "ROT7") (pin "K1") (pinfunction "C_K1") (pintype "passive"))
      (node (ref "ROT7") (pin "K10") (pinfunction "C_K10") (pintype "passive"))
      (node (ref "ROT7") (pin "K12") (pinfunction "C_K12") (pintype "passive"))
      (node (ref "ROT7") (pin "K2") (pinfunction "C_K2") (pintype "passive"))
      (node (ref "ROT7") (pin "K3") (pinfunction "C_K3") (pintype "passive"))
      (node (ref "ROT7") (pin "K4") (pinfunction "C_K4") (pintype "passive"))
      (node (ref "ROT7") (pin "K5") (pinfunction "C_K5") (pintype "passive"))
      (node (ref "ROT7") (pin "K6") (pinfunction "C_K6") (pintype "passive"))
      (node (ref "ROT7") (pin "K7") (pinfunction "C_K7") (pintype "passive"))
      (node (ref "ROT7") (pin "K8") (pinfunction "C_K8") (pintype "passive"))
      (node (ref "ROT7") (pin "K9") (pinfunction "C_K9") (pintype "passive"))
    )
    (net (code "51") (name "Net-(DO_IC7B-3C)") (class "Default")
      (node (ref "DO_IC7B") (pin "16") (pinfunction "3C_16") (pintype "open_collector"))
      (node (ref "ROT6") (pin "K1") (pinfunction "C_K1") (pintype "passive"))
      (node (ref "ROT6") (pin "K10") (pinfunction "C_K10") (pintype "passive"))
      (node (ref "ROT6") (pin "K12") (pinfunction "C_K12") (pintype "passive"))
      (node (ref "ROT6") (pin "K2") (pinfunction "C_K2") (pintype "passive"))
      (node (ref "ROT6") (pin "K3") (pinfunction "C_K3") (pintype "passive"))
      (node (ref "ROT6") (pin "K4") (pinfunction "C_K4") (pintype "passive"))
      (node (ref "ROT6") (pin "K5") (pinfunction "C_K5") (pintype "passive"))
      (node (ref "ROT6") (pin "K6") (pinfunction "C_K6") (pintype "passive"))
      (node (ref "ROT6") (pin "K7") (pinfunction "C_K7") (pintype "passive"))
      (node (ref "ROT6") (pin "K8") (pinfunction "C_K8") (pintype "passive"))
      (node (ref "ROT6") (pin "K9") (pinfunction "C_K9") (pintype "passive"))
    )
    (net (code "52") (name "Net-(DO_IC7B-4C)") (class "Default")
      (node (ref "DO_IC7B") (pin "15") (pinfunction "4C_15") (pintype "open_collector"))
      (node (ref "ROT5") (pin "K1") (pinfunction "C_K1") (pintype "passive"))
      (node (ref "ROT5") (pin "K10") (pinfunction "C_K10") (pintype "passive"))
      (node (ref "ROT5") (pin "K12") (pinfunction "C_K12") (pintype "passive"))
      (node (ref "ROT5") (pin "K2") (pinfunction "C_K2") (pintype "passive"))
      (node (ref "ROT5") (pin "K3") (pinfunction "C_K3") (pintype "passive"))
      (node (ref "ROT5") (pin "K4") (pinfunction "C_K4") (pintype "passive"))
      (node (ref "ROT5") (pin "K5") (pinfunction "C_K5") (pintype "passive"))
      (node (ref "ROT5") (pin "K6") (pinfunction "C_K6") (pintype "passive"))
      (node (ref "ROT5") (pin "K7") (pinfunction "C_K7") (pintype "passive"))
      (node (ref "ROT5") (pin "K8") (pinfunction "C_K8") (pintype "passive"))
      (node (ref "ROT5") (pin "K9") (pinfunction "C_K9") (pintype "passive"))
    )
    (net (code "53") (name "Net-(DO_IC7B-5C)") (class "Default")
      (node (ref "DO_IC7B") (pin "14") (pinfunction "5C_14") (pintype "open_collector"))
      (node (ref "ROT4") (pin "K1") (pinfunction "C_K1") (pintype "passive"))
      (node (ref "ROT4") (pin "K10") (pinfunction "C_K10") (pintype "passive"))
      (node (ref "ROT4") (pin "K12") (pinfunction "C_K12") (pintype "passive"))
      (node (ref "ROT4") (pin "K2") (pinfunction "C_K2") (pintype "passive"))
      (node (ref "ROT4") (pin "K3") (pinfunction "C_K3") (pintype "passive"))
      (node (ref "ROT4") (pin "K4") (pinfunction "C_K4") (pintype "passive"))
      (node (ref "ROT4") (pin "K5") (pinfunction "C_K5") (pintype "passive"))
      (node (ref "ROT4") (pin "K6") (pinfunction "C_K6") (pintype "passive"))
      (node (ref "ROT4") (pin "K7") (pinfunction "C_K7") (pintype "passive"))
      (node (ref "ROT4") (pin "K8") (pinfunction "C_K8") (pintype "passive"))
      (node (ref "ROT4") (pin "K9") (pinfunction "C_K9") (pintype "passive"))
    )
    (net (code "54") (name "Net-(DO_IC7B-6C)") (class "Default")
      (node (ref "DO_IC7B") (pin "13") (pinfunction "6C_13") (pintype "open_collector"))
      (node (ref "ROT3") (pin "K1") (pinfunction "C_K1") (pintype "passive"))
      (node (ref "ROT3") (pin "K10") (pinfunction "C_K10") (pintype "passive"))
      (node (ref "ROT3") (pin "K12") (pinfunction "C_K12") (pintype "passive"))
      (node (ref "ROT3") (pin "K2") (pinfunction "C_K2") (pintype "passive"))
      (node (ref "ROT3") (pin "K3") (pinfunction "C_K3") (pintype "passive"))
      (node (ref "ROT3") (pin "K4") (pinfunction "C_K4") (pintype "passive"))
      (node (ref "ROT3") (pin "K5") (pinfunction "C_K5") (pintype "passive"))
      (node (ref "ROT3") (pin "K6") (pinfunction "C_K6") (pintype "passive"))
      (node (ref "ROT3") (pin "K7") (pinfunction "C_K7") (pintype "passive"))
      (node (ref "ROT3") (pin "K8") (pinfunction "C_K8") (pintype "passive"))
      (node (ref "ROT3") (pin "K9") (pinfunction "C_K9") (pintype "passive"))
    )
    (net (code "55") (name "Net-(DO_IC7B-7C)") (class "Default")
      (node (ref "DO_IC7B") (pin "12") (pinfunction "7C_12") (pintype "open_collector"))
      (node (ref "ROT2") (pin "K1") (pinfunction "C_K1") (pintype "passive"))
      (node (ref "ROT2") (pin "K10") (pinfunction "C_K10") (pintype "passive"))
      (node (ref "ROT2") (pin "K12") (pinfunction "C_K12") (pintype "passive"))
      (node (ref "ROT2") (pin "K2") (pinfunction "C_K2") (pintype "passive"))
      (node (ref "ROT2") (pin "K3") (pinfunction "C_K3") (pintype "passive"))
      (node (ref "ROT2") (pin "K4") (pinfunction "C_K4") (pintype "passive"))
      (node (ref "ROT2") (pin "K5") (pinfunction "C_K5") (pintype "passive"))
      (node (ref "ROT2") (pin "K6") (pinfunction "C_K6") (pintype "passive"))
      (node (ref "ROT2") (pin "K7") (pinfunction "C_K7") (pintype "passive"))
      (node (ref "ROT2") (pin "K8") (pinfunction "C_K8") (pintype "passive"))
      (node (ref "ROT2") (pin "K9") (pinfunction "C_K9") (pintype "passive"))
    )
    (net (code "56") (name "Net-(DO_IC7B-8C)") (class "Default")
      (node (ref "DO_IC7B") (pin "11") (pinfunction "8C_11") (pintype "open_collector"))
      (node (ref "ROT1") (pin "K1") (pinfunction "C_K1") (pintype "passive"))
      (node (ref "ROT1") (pin "K10") (pinfunction "C_K10") (pintype "passive"))
      (node (ref "ROT1") (pin "K12") (pinfunction "C_K12") (pintype "passive"))
      (node (ref "ROT1") (pin "K2") (pinfunction "C_K2") (pintype "passive"))
      (node (ref "ROT1") (pin "K3") (pinfunction "C_K3") (pintype "passive"))
      (node (ref "ROT1") (pin "K4") (pinfunction "C_K4") (pintype "passive"))
      (node (ref "ROT1") (pin "K5") (pinfunction "C_K5") (pintype "passive"))
      (node (ref "ROT1") (pin "K6") (pinfunction "C_K6") (pintype "passive"))
      (node (ref "ROT1") (pin "K7") (pinfunction "C_K7") (pintype "passive"))
      (node (ref "ROT1") (pin "K8") (pinfunction "C_K8") (pintype "passive"))
      (node (ref "ROT1") (pin "K9") (pinfunction "C_K9") (pintype "passive"))
    )
    (net (code "57") (name "Net-(DO_IC8-QA)") (class "Default")
      (node (ref "DO_IC8") (pin "15") (pinfunction "QA_15") (pintype "tri_state"))
      (node (ref "MX_R10") (pin "1") (pinfunction "P$1_1") (pintype "passive"))
    )
    (net (code "58") (name "Net-(DO_IC8-QB)") (class "Default")
      (node (ref "DO_IC8") (pin "1") (pinfunction "QB_1") (pintype "tri_state"))
      (node (ref "MX_R10") (pin "2") (pinfunction "P$2_2") (pintype "passive"))
    )
    (net (code "59") (name "Net-(DO_IC8-QC)") (class "Default")
      (node (ref "DO_IC8") (pin "2") (pinfunction "QC_2") (pintype "tri_state"))
      (node (ref "MX_R10") (pin "3") (pinfunction "P$3_3") (pintype "passive"))
    )
    (net (code "60") (name "Net-(DO_IC8-QD)") (class "Default")
      (node (ref "DO_IC8") (pin "3") (pinfunction "QD_3") (pintype "tri_state"))
      (node (ref "MX_R10") (pin "4") (pinfunction "P$4_4") (pintype "passive"))
    )
    (net (code "61") (name "Net-(DO_IC8-QE)") (class "Default")
      (node (ref "DO_IC8") (pin "4") (pinfunction "QE_4") (pintype "tri_state"))
      (node (ref "MX_R10") (pin "5") (pinfunction "P$5_5") (pintype "passive"))
    )
    (net (code "62") (name "Net-(DO_IC8-QF)") (class "Default")
      (node (ref "DO_IC8") (pin "5") (pinfunction "QF_5") (pintype "tri_state"))
      (node (ref "MX_R10") (pin "6") (pinfunction "P$6_6") (pintype "passive"))
    )
    (net (code "63") (name "Net-(DO_IC8-QG)") (class "Default")
      (node (ref "DO_IC8") (pin "6") (pinfunction "QG_6") (pintype "tri_state"))
      (node (ref "MX_R10") (pin "7") (pinfunction "P$7_7") (pintype "passive"))
    )
    (net (code "64") (name "Net-(DO_IC8-QH)") (class "Default")
      (node (ref "DO_IC8") (pin "7") (pinfunction "QH_7") (pintype "tri_state"))
      (node (ref "MX_R10") (pin "8") (pinfunction "P$8_8") (pintype "passive"))
    )
    (net (code "65") (name "Net-(DO_IC8-QH*)") (class "Default")
      (node (ref "DO_IC8") (pin "9") (pinfunction "QH*_9") (pintype "tri_state"))
      (node (ref "DO_IC9") (pin "14") (pinfunction "SER_14") (pintype "input"))
    )
    (net (code "66") (name "Net-(DO_IC9-QF)") (class "Default")
      (node (ref "DO_IC9") (pin "5") (pinfunction "QF_5") (pintype "tri_state"))
      (node (ref "R13") (pin "2") (pinfunction "2_2") (pintype "passive"))
    )
    (net (code "67") (name "Net-(DO_IC9-QG)") (class "Default")
      (node (ref "DO_IC9") (pin "6") (pinfunction "QG_6") (pintype "tri_state"))
      (node (ref "R12") (pin "2") (pinfunction "2_2") (pintype "passive"))
    )
    (net (code "68") (name "Net-(DO_IC9-QH)") (class "Default")
      (node (ref "DO_IC9") (pin "7") (pinfunction "QH_7") (pintype "tri_state"))
      (node (ref "R11") (pin "2") (pinfunction "2_2") (pintype "passive"))
    )
    (net (code "69") (name "Net-(MX_R10-P$9)") (class "Default")
      (node (ref "MX_R10") (pin "9") (pinfunction "P$9_9") (pintype "passive"))
      (node (ref "ROT1") (pin "A1") (pinfunction "A_A1") (pintype "passive"))
      (node (ref "ROT2") (pin "A1") (pinfunction "A_A1") (pintype "passive"))
      (node (ref "ROT3") (pin "A1") (pinfunction "A_A1") (pintype "passive"))
      (node (ref "ROT4") (pin "A1") (pinfunction "A_A1") (pintype "passive"))
      (node (ref "ROT5") (pin "A1") (pinfunction "A_A1") (pintype "passive"))
      (node (ref "ROT6") (pin "A1") (pinfunction "A_A1") (pintype "passive"))
      (node (ref "ROT7") (pin "A1") (pinfunction "A_A1") (pintype "passive"))
      (node (ref "ROT8") (pin "A1") (pinfunction "A_A1") (pintype "passive"))
    )
    (net (code "70") (name "Net-(MX_R10-P$10)") (class "Default")
      (node (ref "MX_R10") (pin "10") (pinfunction "P$10_10") (pintype "passive"))
      (node (ref "ROT1") (pin "A2") (pinfunction "A_A2") (pintype "passive"))
      (node (ref "ROT2") (pin "A2") (pinfunction "A_A2") (pintype "passive"))
      (node (ref "ROT3") (pin "A2") (pinfunction "A_A2") (pintype "passive"))
      (node (ref "ROT4") (pin "A2") (pinfunction "A_A2") (pintype "passive"))
      (node (ref "ROT5") (pin "A2") (pinfunction "A_A2") (pintype "passive"))
      (node (ref "ROT6") (pin "A2") (pinfunction "A_A2") (pintype "passive"))
      (node (ref "ROT7") (pin "A2") (pinfunction "A_A2") (pintype "passive"))
      (node (ref "ROT8") (pin "A2") (pinfunction "A_A2") (pintype "passive"))
    )
    (net (code "71") (name "Net-(MX_R10-P$11)") (class "Default")
      (node (ref "MX_R10") (pin "11") (pinfunction "P$11_11") (pintype "passive"))
      (node (ref "ROT1") (pin "A3") (pinfunction "A_A3") (pintype "passive"))
      (node (ref "ROT2") (pin "A3") (pinfunction "A_A3") (pintype "passive"))
      (node (ref "ROT3") (pin "A3") (pinfunction "A_A3") (pintype "passive"))
      (node (ref "ROT4") (pin "A3") (pinfunction "A_A3") (pintype "passive"))
      (node (ref "ROT5") (pin "A3") (pinfunction "A_A3") (pintype "passive"))
      (node (ref "ROT6") (pin "A3") (pinfunction "A_A3") (pintype "passive"))
      (node (ref "ROT7") (pin "A3") (pinfunction "A_A3") (pintype "passive"))
      (node (ref "ROT8") (pin "A3") (pinfunction "A_A3") (pintype "passive"))
    )
    (net (code "72") (name "Net-(MX_R10-P$12)") (class "Default")
      (node (ref "MX_R10") (pin "12") (pinfunction "P$12_12") (pintype "passive"))
      (node (ref "ROT1") (pin "A4") (pinfunction "A_A4") (pintype "passive"))
      (node (ref "ROT2") (pin "A4") (pinfunction "A_A4") (pintype "passive"))
      (node (ref "ROT3") (pin "A4") (pinfunction "A_A4") (pintype "passive"))
      (node (ref "ROT4") (pin "A4") (pinfunction "A_A4") (pintype "passive"))
      (node (ref "ROT5") (pin "A4") (pinfunction "A_A4") (pintype "passive"))
      (node (ref "ROT6") (pin "A4") (pinfunction "A_A4") (pintype "passive"))
      (node (ref "ROT7") (pin "A4") (pinfunction "A_A4") (pintype "passive"))
      (node (ref "ROT8") (pin "A4") (pinfunction "A_A4") (pintype "passive"))
    )
    (net (code "73") (name "Net-(MX_R10-P$13)") (class "Default")
      (node (ref "MX_R10") (pin "13") (pinfunction "P$13_13") (pintype "passive"))
      (node (ref "ROT1") (pin "A5") (pinfunction "A_A5") (pintype "passive"))
      (node (ref "ROT2") (pin "A5") (pinfunction "A_A5") (pintype "passive"))
      (node (ref "ROT3") (pin "A5") (pinfunction "A_A5") (pintype "passive"))
      (node (ref "ROT4") (pin "A5") (pinfunction "A_A5") (pintype "passive"))
      (node (ref "ROT5") (pin "A5") (pinfunction "A_A5") (pintype "passive"))
      (node (ref "ROT6") (pin "A5") (pinfunction "A_A5") (pintype "passive"))
      (node (ref "ROT7") (pin "A5") (pinfunction "A_A5") (pintype "passive"))
      (node (ref "ROT8") (pin "A5") (pinfunction "A_A5") (pintype "passive"))
    )
    (net (code "74") (name "Net-(MX_R10-P$14)") (class "Default")
      (node (ref "MX_R10") (pin "14") (pinfunction "P$14_14") (pintype "passive"))
      (node (ref "ROT1") (pin "A6") (pinfunction "A_A6") (pintype "passive"))
      (node (ref "ROT2") (pin "A6") (pinfunction "A_A6") (pintype "passive"))
      (node (ref "ROT3") (pin "A6") (pinfunction "A_A6") (pintype "passive"))
      (node (ref "ROT4") (pin "A6") (pinfunction "A_A6") (pintype "passive"))
      (node (ref "ROT5") (pin "A6") (pinfunction "A_A6") (pintype "passive"))
      (node (ref "ROT6") (pin "A6") (pinfunction "A_A6") (pintype "passive"))
      (node (ref "ROT7") (pin "A6") (pinfunction "A_A6") (pintype "passive"))
      (node (ref "ROT8") (pin "A6") (pinfunction "A_A6") (pintype "passive"))
    )
    (net (code "75") (name "Net-(MX_R10-P$15)") (class "Default")
      (node (ref "MX_R10") (pin "15") (pinfunction "P$15_15") (pintype "passive"))
      (node (ref "ROT1") (pin "A7") (pinfunction "A_A7") (pintype "passive"))
      (node (ref "ROT2") (pin "A7") (pinfunction "A_A7") (pintype "passive"))
      (node (ref "ROT3") (pin "A7") (pinfunction "A_A7") (pintype "passive"))
      (node (ref "ROT4") (pin "A7") (pinfunction "A_A7") (pintype "passive"))
      (node (ref "ROT5") (pin "A7") (pinfunction "A_A7") (pintype "passive"))
      (node (ref "ROT6") (pin "A7") (pinfunction "A_A7") (pintype "passive"))
      (node (ref "ROT7") (pin "A7") (pinfunction "A_A7") (pintype "passive"))
      (node (ref "ROT8") (pin "A7") (pinfunction "A_A7") (pintype "passive"))
    )
    (net (code "76") (name "Net-(MX_R10-P$16)") (class "Default")
      (node (ref "MX_R10") (pin "16") (pinfunction "P$16_16") (pintype "passive"))
      (node (ref "ROT1") (pin "A8") (pinfunction "A_A8") (pintype "passive"))
      (node (ref "ROT2") (pin "A8") (pinfunction "A_A8") (pintype "passive"))
      (node (ref "ROT3") (pin "A8") (pinfunction "A_A8") (pintype "passive"))
      (node (ref "ROT4") (pin "A8") (pinfunction "A_A8") (pintype "passive"))
      (node (ref "ROT5") (pin "A8") (pinfunction "A_A8") (pintype "passive"))
      (node (ref "ROT6") (pin "A8") (pinfunction "A_A8") (pintype "passive"))
      (node (ref "ROT7") (pin "A8") (pinfunction "A_A8") (pintype "passive"))
      (node (ref "ROT8") (pin "A8") (pinfunction "A_A8") (pintype "passive"))
    )
    (net (code "77") (name "Net-(ROT1C-A)") (class "Default")
      (node (ref "R12") (pin "1") (pinfunction "1_1") (pintype "passive"))
      (node (ref "ROT1") (pin "A10") (pinfunction "A_A10") (pintype "passive"))
      (node (ref "ROT2") (pin "A10") (pinfunction "A_A10") (pintype "passive"))
      (node (ref "ROT3") (pin "A10") (pinfunction "A_A10") (pintype "passive"))
      (node (ref "ROT4") (pin "A10") (pinfunction "A_A10") (pintype "passive"))
      (node (ref "ROT5") (pin "A10") (pinfunction "A_A10") (pintype "passive"))
      (node (ref "ROT6") (pin "A10") (pinfunction "A_A10") (pintype "passive"))
      (node (ref "ROT7") (pin "A10") (pinfunction "A_A10") (pintype "passive"))
      (node (ref "ROT8") (pin "A10") (pinfunction "A_A10") (pintype "passive"))
    )
    (net (code "78") (name "Net-(ROT1D-A)") (class "Default")
      (node (ref "R13") (pin "1") (pinfunction "1_1") (pintype "passive"))
      (node (ref "ROT1") (pin "A12") (pinfunction "A_A12") (pintype "passive"))
      (node (ref "ROT2") (pin "A12") (pinfunction "A_A12") (pintype "passive"))
      (node (ref "ROT3") (pin "A12") (pinfunction "A_A12") (pintype "passive"))
      (node (ref "ROT4") (pin "A12") (pinfunction "A_A12") (pintype "passive"))
      (node (ref "ROT5") (pin "A12") (pinfunction "A_A12") (pintype "passive"))
      (node (ref "ROT6") (pin "A12") (pinfunction "A_A12") (pintype "passive"))
      (node (ref "ROT7") (pin "A12") (pinfunction "A_A12") (pintype "passive"))
      (node (ref "ROT8") (pin "A12") (pinfunction "A_A12") (pintype "passive"))
    )
    (net (code "79") (name "Net-(ROT1L-A)") (class "Default")
      (node (ref "R11") (pin "1") (pinfunction "1_1") (pintype "passive"))
      (node (ref "ROT1") (pin "A9") (pinfunction "A_A9") (pintype "passive"))
      (node (ref "ROT2") (pin "A9") (pinfunction "A_A9") (pintype "passive"))
      (node (ref "ROT3") (pin "A9") (pinfunction "A_A9") (pintype "passive"))
      (node (ref "ROT4") (pin "A9") (pinfunction "A_A9") (pintype "passive"))
      (node (ref "ROT5") (pin "A9") (pinfunction "A_A9") (pintype "passive"))
      (node (ref "ROT6") (pin "A9") (pinfunction "A_A9") (pintype "passive"))
      (node (ref "ROT7") (pin "A9") (pinfunction "A_A9") (pintype "passive"))
      (node (ref "ROT8") (pin "A9") (pinfunction "A_A9") (pintype "passive"))
    )
    (net (code "80") (name "R1B") (class "Default")
      (node (ref "DO_R7") (pin "16") (pinfunction "P$16_16") (pintype "passive"))
      (node (ref "ROT1") (pin "LED_BLUE") (pinfunction "LED_BLUE_LED_BLUE") (pintype "bidirectional"))
    )
    (net (code "81") (name "R1G") (class "Default")
      (node (ref "DO_R6") (pin "8") (pinfunction "P$8_8") (pintype "passive"))
      (node (ref "ROT1") (pin "LED_GREEN") (pinfunction "LED_GREEN_LED_GREEN") (pintype "bidirectional"))
    )
    (net (code "82") (name "R1R") (class "Default")
      (node (ref "DO_R5") (pin "8") (pinfunction "P$8_8") (pintype "passive"))
      (node (ref "ROT1") (pin "LED_RED") (pinfunction "LED_RED_LED_RED") (pintype "bidirectional"))
    )
    (net (code "83") (name "R2B") (class "Default")
      (node (ref "DO_R7") (pin "15") (pinfunction "P$15_15") (pintype "passive"))
      (node (ref "ROT2") (pin "LED_BLUE") (pinfunction "LED_BLUE_LED_BLUE") (pintype "bidirectional"))
    )
    (net (code "84") (name "R2G") (class "Default")
      (node (ref "DO_R6") (pin "7") (pinfunction "P$7_7") (pintype "passive"))
      (node (ref "ROT2") (pin "LED_GREEN") (pinfunction "LED_GREEN_LED_GREEN") (pintype "bidirectional"))
    )
    (net (code "85") (name "R2R") (class "Default")
      (node (ref "DO_R5") (pin "7") (pinfunction "P$7_7") (pintype "passive"))
      (node (ref "ROT2") (pin "LED_RED") (pinfunction "LED_RED_LED_RED") (pintype "bidirectional"))
    )
    (net (code "86") (name "R3B") (class "Default")
      (node (ref "DO_R7") (pin "14") (pinfunction "P$14_14") (pintype "passive"))
      (node (ref "ROT3") (pin "LED_BLUE") (pinfunction "LED_BLUE_LED_BLUE") (pintype "bidirectional"))
    )
    (net (code "87") (name "R3G") (class "Default")
      (node (ref "DO_R6") (pin "6") (pinfunction "P$6_6") (pintype "passive"))
      (node (ref "ROT3") (pin "LED_GREEN") (pinfunction "LED_GREEN_LED_GREEN") (pintype "bidirectional"))
    )
    (net (code "88") (name "R3R") (class "Default")
      (node (ref "DO_R5") (pin "6") (pinfunction "P$6_6") (pintype "passive"))
      (node (ref "ROT3") (pin "LED_RED") (pinfunction "LED_RED_LED_RED") (pintype "bidirectional"))
    )
    (net (code "89") (name "R4B") (class "Default")
      (node (ref "DO_R7") (pin "13") (pinfunction "P$13_13") (pintype "passive"))
      (node (ref "ROT4") (pin "LED_BLUE") (pinfunction "LED_BLUE_LED_BLUE") (pintype "bidirectional"))
    )
    (net (code "90") (name "R4G") (class "Default")
      (node (ref "DO_R6") (pin "5") (pinfunction "P$5_5") (pintype "passive"))
      (node (ref "ROT4") (pin "LED_GREEN") (pinfunction "LED_GREEN_LED_GREEN") (pintype "bidirectional"))
    )
    (net (code "91") (name "R4R") (class "Default")
      (node (ref "DO_R5") (pin "5") (pinfunction "P$5_5") (pintype "passive"))
      (node (ref "ROT4") (pin "LED_RED") (pinfunction "LED_RED_LED_RED") (pintype "bidirectional"))
    )
    (net (code "92") (name "R5B") (class "Default")
      (node (ref "DO_R7") (pin "12") (pinfunction "P$12_12") (pintype "passive"))
      (node (ref "ROT5") (pin "LED_BLUE") (pinfunction "LED_BLUE_LED_BLUE") (pintype "bidirectional"))
    )
    (net (code "93") (name "R5G") (class "Default")
      (node (ref "DO_R6") (pin "4") (pinfunction "P$4_4") (pintype "passive"))
      (node (ref "ROT5") (pin "LED_GREEN") (pinfunction "LED_GREEN_LED_GREEN") (pintype "bidirectional"))
    )
    (net (code "94") (name "R5R") (class "Default")
      (node (ref "DO_R5") (pin "4") (pinfunction "P$4_4") (pintype "passive"))
      (node (ref "ROT5") (pin "LED_RED") (pinfunction "LED_RED_LED_RED") (pintype "bidirectional"))
    )
    (net (code "95") (name "R6B") (class "Default")
      (node (ref "DO_R7") (pin "11") (pinfunction "P$11_11") (pintype "passive"))
      (node (ref "ROT6") (pin "LED_BLUE") (pinfunction "LED_BLUE_LED_BLUE") (pintype "bidirectional"))
    )
    (net (code "96") (name "R6G") (class "Default")
      (node (ref "DO_R6") (pin "3") (pinfunction "P$3_3") (pintype "passive"))
      (node (ref "ROT6") (pin "LED_GREEN") (pinfunction "LED_GREEN_LED_GREEN") (pintype "bidirectional"))
    )
    (net (code "97") (name "R6R") (class "Default")
      (node (ref "DO_R5") (pin "3") (pinfunction "P$3_3") (pintype "passive"))
      (node (ref "ROT6") (pin "LED_RED") (pinfunction "LED_RED_LED_RED") (pintype "bidirectional"))
    )
    (net (code "98") (name "R7B") (class "Default")
      (node (ref "DO_R7") (pin "10") (pinfunction "P$10_10") (pintype "passive"))
      (node (ref "ROT7") (pin "LED_BLUE") (pinfunction "LED_BLUE_LED_BLUE") (pintype "bidirectional"))
    )
    (net (code "99") (name "R7G") (class "Default")
      (node (ref "DO_R6") (pin "2") (pinfunction "P$2_2") (pintype "passive"))
      (node (ref "ROT7") (pin "LED_GREEN") (pinfunction "LED_GREEN_LED_GREEN") (pintype "bidirectional"))
    )
    (net (code "100") (name "R7R") (class "Default")
      (node (ref "DO_R5") (pin "2") (pinfunction "P$2_2") (pintype "passive"))
      (node (ref "ROT7") (pin "LED_RED") (pinfunction "LED_RED_LED_RED") (pintype "bidirectional"))
    )
    (net (code "101") (name "R8B") (class "Default")
      (node (ref "DO_R7") (pin "9") (pinfunction "P$9_9") (pintype "passive"))
      (node (ref "ROT8") (pin "LED_BLUE") (pinfunction "LED_BLUE_LED_BLUE") (pintype "bidirectional"))
    )
    (net (code "102") (name "R8G") (class "Default")
      (node (ref "DO_R6") (pin "1") (pinfunction "P$1_1") (pintype "passive"))
      (node (ref "ROT8") (pin "LED_GREEN") (pinfunction "LED_GREEN_LED_GREEN") (pintype "bidirectional"))
    )
    (net (code "103") (name "R8R") (class "Default")
      (node (ref "DO_R5") (pin "1") (pinfunction "P$1_1") (pintype "passive"))
      (node (ref "ROT8") (pin "LED_RED") (pinfunction "LED_RED_LED_RED") (pintype "bidirectional"))
    )
    (net (code "104") (name "RC-I") (class "Default")
      (node (ref "DI_IC1") (pin "1") (pinfunction "SH/~{LD}_1") (pintype "input"))
      (node (ref "DI_IC2") (pin "1") (pinfunction "SH/~{LD}_1") (pintype "input"))
      (node (ref "DI_IC3") (pin "1") (pinfunction "SH/~{LD}_1") (pintype "input"))
      (node (ref "J1") (pin "9") (pinfunction "9_9") (pintype "passive"))
      (node (ref "J2") (pin "9") (pinfunction "9_9") (pintype "passive"))
    )
    (net (code "105") (name "RC-O") (class "Default")
      (node (ref "DO_IC4_R") (pin "12") (pinfunction "RCK_12") (pintype "input"))
      (node (ref "DO_IC5_G") (pin "12") (pinfunction "RCK_12") (pintype "input"))
      (node (ref "DO_IC6_B") (pin "12") (pinfunction "RCK_12") (pintype "input"))
      (node (ref "DO_IC7") (pin "12") (pinfunction "RCK_12") (pintype "input"))
      (node (ref "DO_IC8") (pin "12") (pinfunction "RCK_12") (pintype "input"))
      (node (ref "DO_IC9") (pin "12") (pinfunction "RCK_12") (pintype "input"))
      (node (ref "J1") (pin "10") (pinfunction "10_10") (pintype "passive"))
      (node (ref "J2") (pin "10") (pinfunction "10_10") (pintype "passive"))
    )
    (net (code "106") (name "ROT1A") (class "Default")
      (node (ref "DI_IC1") (pin "12") (pinfunction "I2_12") (pintype "input"))
      (node (ref "DI_R2") (pin "4") (pinfunction "4_4") (pintype "passive"))
      (node (ref "ROT1") (pin "A") (pinfunction "A_A") (pintype "bidirectional"))
    )
    (net (code "107") (name "ROT1B") (class "Default")
      (node (ref "DI_IC1") (pin "11") (pinfunction "I1_11") (pintype "input"))
      (node (ref "DI_R2") (pin "5") (pinfunction "5_5") (pintype "passive"))
      (node (ref "ROT1") (pin "B") (pinfunction "B_B") (pintype "bidirectional"))
    )
    (net (code "108") (name "ROT2A") (class "Default")
      (node (ref "DI_IC1") (pin "14") (pinfunction "I4_14") (pintype "input"))
      (node (ref "DI_R2") (pin "2") (pinfunction "2_2") (pintype "passive"))
      (node (ref "ROT2") (pin "A") (pinfunction "A_A") (pintype "bidirectional"))
    )
    (net (code "109") (name "ROT2B") (class "Default")
      (node (ref "DI_IC1") (pin "13") (pinfunction "I3_13") (pintype "input"))
      (node (ref "DI_R2") (pin "3") (pinfunction "3_3") (pintype "passive"))
      (node (ref "ROT2") (pin "B") (pinfunction "B_B") (pintype "bidirectional"))
    )
    (net (code "110") (name "ROT3A") (class "Default")
      (node (ref "DI_IC1") (pin "4") (pinfunction "I6_4") (pintype "input"))
      (node (ref "DI_R1") (pin "3") (pinfunction "3_3") (pintype "passive"))
      (node (ref "ROT3") (pin "A") (pinfunction "A_A") (pintype "bidirectional"))
    )
    (net (code "111") (name "ROT3B") (class "Default")
      (node (ref "DI_IC1") (pin "3") (pinfunction "I5_3") (pintype "input"))
      (node (ref "DI_R1") (pin "2") (pinfunction "2_2") (pintype "passive"))
      (node (ref "ROT3") (pin "B") (pinfunction "B_B") (pintype "bidirectional"))
    )
    (net (code "112") (name "ROT4A") (class "Default")
      (node (ref "DI_IC1") (pin "6") (pinfunction "I8_6") (pintype "input"))
      (node (ref "DI_R1") (pin "5") (pinfunction "5_5") (pintype "passive"))
      (node (ref "ROT4") (pin "A") (pinfunction "A_A") (pintype "bidirectional"))
    )
    (net (code "113") (name "ROT4B") (class "Default")
      (node (ref "DI_IC1") (pin "5") (pinfunction "I7_5") (pintype "input"))
      (node (ref "DI_R1") (pin "4") (pinfunction "4_4") (pintype "passive"))
      (node (ref "ROT4") (pin "B") (pinfunction "B_B") (pintype "bidirectional"))
    )
    (net (code "114") (name "ROT5A") (class "Default")
      (node (ref "DI_IC2") (pin "12") (pinfunction "I2_12") (pintype "input"))
      (node (ref "DI_R4") (pin "4") (pinfunction "4_4") (pintype "passive"))
      (node (ref "ROT5") (pin "A") (pinfunction "A_A") (pintype "bidirectional"))
    )
    (net (code "115") (name "ROT5B") (class "Default")
      (node (ref "DI_IC2") (pin "11") (pinfunction "I1_11") (pintype "input"))
      (node (ref "DI_R4") (pin "5") (pinfunction "5_5") (pintype "passive"))
      (node (ref "ROT5") (pin "B") (pinfunction "B_B") (pintype "bidirectional"))
    )
    (net (code "116") (name "ROT6A") (class "Default")
      (node (ref "DI_IC2") (pin "14") (pinfunction "I4_14") (pintype "input"))
      (node (ref "DI_R4") (pin "2") (pinfunction "2_2") (pintype "passive"))
      (node (ref "ROT6") (pin "A") (pinfunction "A_A") (pintype "bidirectional"))
    )
    (net (code "117") (name "ROT6B") (class "Default")
      (node (ref "DI_IC2") (pin "13") (pinfunction "I3_13") (pintype "input"))
      (node (ref "DI_R4") (pin "3") (pinfunction "3_3") (pintype "passive"))
      (node (ref "ROT6") (pin "B") (pinfunction "B_B") (pintype "bidirectional"))
    )
    (net (code "118") (name "ROT7A") (class "Default")
      (node (ref "DI_IC2") (pin "4") (pinfunction "I6_4") (pintype "input"))
      (node (ref "DI_R3") (pin "3") (pinfunction "3_3") (pintype "passive"))
      (node (ref "ROT7") (pin "A") (pinfunction "A_A") (pintype "bidirectional"))
    )
    (net (code "119") (name "ROT7B") (class "Default")
      (node (ref "DI_IC2") (pin "3") (pinfunction "I5_3") (pintype "input"))
      (node (ref "DI_R3") (pin "2") (pinfunction "2_2") (pintype "passive"))
      (node (ref "ROT7") (pin "B") (pinfunction "B_B") (pintype "bidirectional"))
    )
    (net (code "120") (name "ROT8A") (class "Default")
      (node (ref "DI_IC2") (pin "6") (pinfunction "I8_6") (pintype "input"))
      (node (ref "DI_R3") (pin "5") (pinfunction "5_5") (pintype "passive"))
      (node (ref "ROT8") (pin "A") (pinfunction "A_A") (pintype "bidirectional"))
    )
    (net (code "121") (name "ROT8B") (class "Default")
      (node (ref "DI_IC2") (pin "5") (pinfunction "I7_5") (pintype "input"))
      (node (ref "DI_R3") (pin "4") (pinfunction "4_4") (pintype "passive"))
      (node (ref "ROT8") (pin "B") (pinfunction "B_B") (pintype "bidirectional"))
    )
    (net (code "122") (name "SC") (class "Default")
      (node (ref "DI_IC1") (pin "2") (pinfunction "CLK_2") (pintype "input"))
      (node (ref "DI_IC2") (pin "2") (pinfunction "CLK_2") (pintype "input"))
      (node (ref "DI_IC3") (pin "2") (pinfunction "CLK_2") (pintype "input"))
      (node (ref "DO_IC4_R") (pin "13") (pinfunction "SCK_13") (pintype "input"))
      (node (ref "DO_IC5_G") (pin "13") (pinfunction "SCK_13") (pintype "input"))
      (node (ref "DO_IC6_B") (pin "13") (pinfunction "SCK_13") (pintype "input"))
      (node (ref "DO_IC7") (pin "11") (pinfunction "SCK_11") (pintype "input"))
      (node (ref "DO_IC8") (pin "11") (pinfunction "SCK_11") (pintype "input"))
      (node (ref "DO_IC9") (pin "11") (pinfunction "SCK_11") (pintype "input"))
      (node (ref "J1") (pin "7") (pinfunction "7_7") (pintype "passive"))
      (node (ref "J1") (pin "8") (pinfunction "8_8") (pintype "passive"))
      (node (ref "J2") (pin "7") (pinfunction "7_7") (pintype "passive"))
      (node (ref "J2") (pin "8") (pinfunction "8_8") (pintype "passive"))
    )
    (net (code "123") (name "SI-INPUT") (class "Default")
      (node (ref "DI_IC3") (pin "10") (pinfunction "SER_10") (pintype "input"))
      (node (ref "DI_R6") (pin "6") (pinfunction "6_6") (pintype "passive"))
      (node (ref "J2") (pin "5") (pinfunction "5_5") (pintype "passive"))
    )
    (net (code "124") (name "SI-OUTPUT") (class "Default")
      (node (ref "DI_IC1") (pin "9") (pinfunction "QH_9") (pintype "output"))
      (node (ref "J1") (pin "5") (pinfunction "5_5") (pintype "passive"))
    )
    (net (code "125") (name "SO-INPUT") (class "Default")
      (node (ref "DO_IC4_R") (pin "3") (pinfunction "SER_3") (pintype "input"))
      (node (ref "J1") (pin "6") (pinfunction "6_6") (pintype "passive"))
    )
    (net (code "126") (name "SO-OUTPUT") (class "Default")
      (node (ref "DO_IC9") (pin "9") (pinfunction "QH*_9") (pintype "tri_state"))
      (node (ref "J2") (pin "6") (pinfunction "6_6") (pintype "passive"))
    )
    (net (code "127") (name "SW1") (class "Default")
      (node (ref "DI_IC3B") (pin "8") (pinfunction "8B_8") (pintype "input"))
      (node (ref "ROT1") (pin "SWITCH") (pinfunction "SW_SWITCH") (pintype "bidirectional"))
    )
    (net (code "128") (name "SW2") (class "Default")
      (node (ref "DI_IC3B") (pin "7") (pinfunction "7B_7") (pintype "input"))
      (node (ref "ROT2") (pin "SWITCH") (pinfunction "SW_SWITCH") (pintype "bidirectional"))
    )
    (net (code "129") (name "SW3") (class "Default")
      (node (ref "DI_IC3B") (pin "6") (pinfunction "6B_6") (pintype "input"))
      (node (ref "ROT3") (pin "SWITCH") (pinfunction "SW_SWITCH") (pintype "bidirectional"))
    )
    (net (code "130") (name "SW4") (class "Default")
      (node (ref "DI_IC3B") (pin "5") (pinfunction "5B_5") (pintype "input"))
      (node (ref "ROT4") (pin "SWITCH") (pinfunction "SW_SWITCH") (pintype "bidirectional"))
    )
    (net (code "131") (name "SW5") (class "Default")
      (node (ref "DI_IC3B") (pin "4") (pinfunction "4B_4") (pintype "input"))
      (node (ref "ROT5") (pin "SWITCH") (pinfunction "SW_SWITCH") (pintype "bidirectional"))
    )
    (net (code "132") (name "SW6") (class "Default")
      (node (ref "DI_IC3B") (pin "3") (pinfunction "3B_3") (pintype "input"))
      (node (ref "ROT6") (pin "SWITCH") (pinfunction "SW_SWITCH") (pintype "bidirectional"))
    )
    (net (code "133") (name "SW7") (class "Default")
      (node (ref "DI_IC3B") (pin "2") (pinfunction "2B_2") (pintype "input"))
      (node (ref "ROT7") (pin "SWITCH") (pinfunction "SW_SWITCH") (pintype "bidirectional"))
    )
    (net (code "134") (name "SW8") (class "Default")
      (node (ref "DI_IC3B") (pin "1") (pinfunction "1B_1") (pintype "input"))
      (node (ref "ROT8") (pin "SWITCH") (pinfunction "SW_SWITCH") (pintype "bidirectional"))
    )
    (net (code "135") (name "unconnected-(DI_IC1-~{QH}-Pad7)") (class "Default")
      (node (ref "DI_IC1") (pin "7") (pinfunction "~{QH}_7") (pintype "output"))
    )
    (net (code "136") (name "unconnected-(DI_IC2-~{QH}-Pad7)") (class "Default")
      (node (ref "DI_IC2") (pin "7") (pinfunction "~{QH}_7") (pintype "output"))
    )
    (net (code "137") (name "unconnected-(DI_IC3-~{QH}-Pad7)") (class "Default")
      (node (ref "DI_IC3") (pin "7") (pinfunction "~{QH}_7") (pintype "output"))
    )
    (net (code "138") (name "unconnected-(DI_IC3B-C-Pad10)") (class "Default")
      (node (ref "DI_IC3B") (pin "10") (pinfunction "C_10") (pintype "passive"))
    )
    (net (code "139") (name "unconnected-(DI_R2-Pad6)") (class "Default")
      (node (ref "DI_R2") (pin "6") (pinfunction "6_6") (pintype "passive"))
    )
    (net (code "140") (name "unconnected-(DI_R3-Pad6)") (class "Default")
      (node (ref "DI_R3") (pin "6") (pinfunction "6_6") (pintype "passive"))
    )
    (net (code "141") (name "unconnected-(DI_R5-Pad6)") (class "Default")
      (node (ref "DI_R5") (pin "6") (pinfunction "6_6") (pintype "passive"))
    )
    (net (code "142") (name "unconnected-(DO_IC4_R-NC-Pad20)") (class "Default")
      (node (ref "DO_IC4_R") (pin "20") (pinfunction "NC_20") (pintype "no_connect"))
    )
    (net (code "143") (name "unconnected-(DO_IC4_R-NC1-Pad1)") (class "Default")
      (node (ref "DO_IC4_R") (pin "1") (pinfunction "NC1_1") (pintype "no_connect"))
    )
    (net (code "144") (name "unconnected-(DO_IC5_G-NC-Pad20)") (class "Default")
      (node (ref "DO_IC5_G") (pin "20") (pinfunction "NC_20") (pintype "no_connect"))
    )
    (net (code "145") (name "unconnected-(DO_IC5_G-NC1-Pad1)") (class "Default")
      (node (ref "DO_IC5_G") (pin "1") (pinfunction "NC1_1") (pintype "no_connect"))
    )
    (net (code "146") (name "unconnected-(DO_IC6_B-NC-Pad20)") (class "Default")
      (node (ref "DO_IC6_B") (pin "20") (pinfunction "NC_20") (pintype "no_connect"))
    )
    (net (code "147") (name "unconnected-(DO_IC6_B-NC1-Pad1)") (class "Default")
      (node (ref "DO_IC6_B") (pin "1") (pinfunction "NC1_1") (pintype "no_connect"))
    )
    (net (code "148") (name "unconnected-(DO_IC9-QA-Pad15)") (class "Default")
      (node (ref "DO_IC9") (pin "15") (pinfunction "QA_15") (pintype "tri_state"))
    )
    (net (code "149") (name "unconnected-(DO_IC9-QB-Pad1)") (class "Default")
      (node (ref "DO_IC9") (pin "1") (pinfunction "QB_1") (pintype "tri_state"))
    )
    (net (code "150") (name "unconnected-(DO_IC9-QC-Pad2)") (class "Default")
      (node (ref "DO_IC9") (pin "2") (pinfunction "QC_2") (pintype "tri_state"))
    )
    (net (code "151") (name "unconnected-(DO_IC9-QD-Pad3)") (class "Default")
      (node (ref "DO_IC9") (pin "3") (pinfunction "QD_3") (pintype "tri_state"))
    )
    (net (code "152") (name "unconnected-(DO_IC9-QE-Pad4)") (class "Default")
      (node (ref "DO_IC9") (pin "4") (pinfunction "QE_4") (pintype "tri_state"))
    )
  )
)
